# USBA1P_0v0.net
KiCad netlist of a schematic drawn in EAGLE
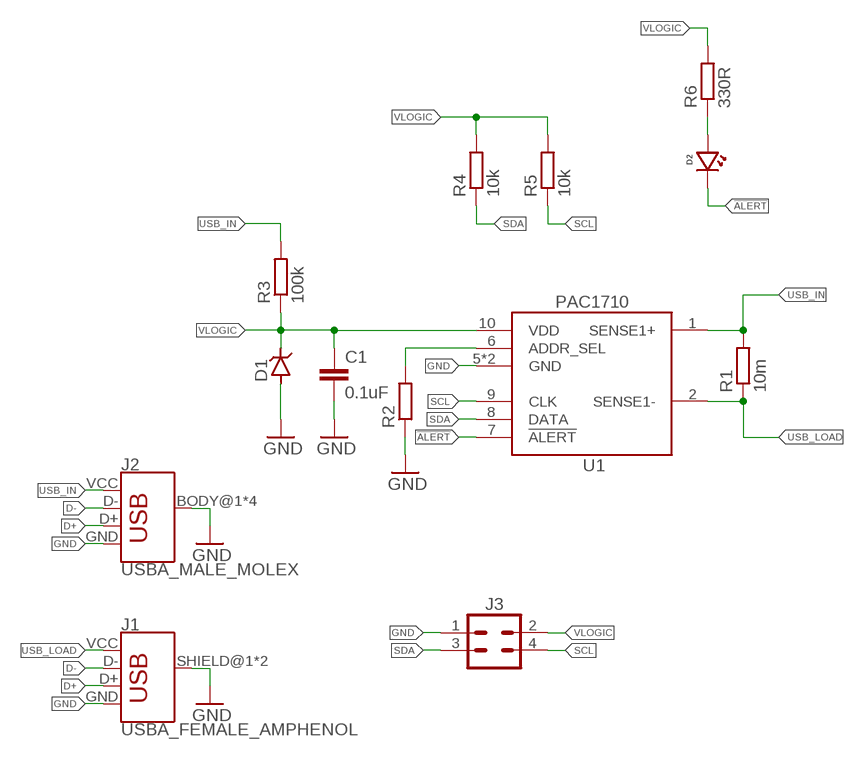
[diagram p0: schematic, sheet 1]

(export (version "E")
  (design (tool "Eeschema 10.0.6"))
  (components
    (comp (ref "C1")
      (value "0.1uF")
      (footprint "eagle-import:C0603")
      (fields (field (name "MF") "Murata") (field (name "MPN") "GCM188R71E104KA57D"))
      (libsource (lib "eagle-import") (part "C-EUC06030.1UF"))
    )
    (comp (ref "D1")
      (value "DIODE_ZENERSOD-123")
      (footprint "eagle-import:SOD-123")
      (libsource (lib "eagle-import") (part "DIODE_ZENERSOD-123"))
    )
    (comp (ref "D2")
      (value "LED1206_BOTTOM")
      (footprint "eagle-import:LED_1206_BOTTOM")
      (libsource (lib "eagle-import") (part "LED1206_BOTTOM"))
    )
    (comp (ref "J1")
      (value "USBA_FEMALE_AMPHENOL")
      (footprint "eagle-import:USB_A_FEMALE_AMPHENOL")
      (fields (field (name "MF") "Amphenol") (field (name "MPN") "UE27AC54100"))
      (libsource (lib "eagle-import") (part "USBA_FEMALE_AMPHENOL"))
    )
    (comp (ref "J2")
      (value "USBA_MALE_MOLEX")
      (footprint "eagle-import:USB_A_MALE_0480372200")
      (fields (field (name "MF") "Molex") (field (name "MPN") "0480372200"))
      (libsource (lib "eagle-import") (part "USBA_MALE_MOLEX"))
    )
    (comp (ref "J3")
      (value "CONN_2X2MIRCOFIT_RT")
      (footprint "eagle-import:2X2_MICROFIT_RT")
      (fields (field (name "MF") "Molex") (field (name "MPN") "0430450400"))
      (libsource (lib "eagle-import") (part "CONN_2X2MIRCOFIT_RT"))
    )
    (comp (ref "R1")
      (value "10m")
      (footprint "eagle-import:R0805")
      (fields (field (name "MF") "Bourns") (field (name "MPN") "CRF0805-FZ-R010ELF"))
      (libsource (lib "eagle-import") (part "R-EU_R08050.01"))
    )
    (comp (ref "R2")
      (value "R-EU_R0603")
      (footprint "eagle-import:R0603")
      (fields (field (name "MF") "Yageo"))
      (libsource (lib "eagle-import") (part "R-EU_R0603"))
    )
    (comp (ref "R3")
      (value "100k")
      (footprint "eagle-import:R0603")
      (fields (field (name "MF") "Yageo") (field (name "MPN") "RC0603FR-07100KL"))
      (libsource (lib "eagle-import") (part "R-EU_R0603100K"))
    )
    (comp (ref "R4")
      (value "10k")
      (footprint "eagle-import:R0603")
      (fields (field (name "MF") "Yageo") (field (name "MPN") "RC0603FR-0710KL"))
      (libsource (lib "eagle-import") (part "R-EU_R060310K"))
    )
    (comp (ref "R5")
      (value "10k")
      (footprint "eagle-import:R0603")
      (fields (field (name "MF") "Yageo") (field (name "MPN") "RC0603FR-0710KL"))
      (libsource (lib "eagle-import") (part "R-EU_R060310K"))
    )
    (comp (ref "R6")
      (value "330R")
      (footprint "eagle-import:R0603")
      (fields
        (field (name "MF") "Yageo")
        (field (name "MPN") "RC0603FR-07330RL")
        (field (name "VALUE_PART") "330")
      )
      (libsource (lib "eagle-import") (part "R-EU_R0603330"))
    )
    (comp (ref "U1")
      (value "PAC1710")
      (footprint "eagle-import:VDFN-10")
      (fields (field (name "MF") "Microchip") (field (name "MPN") "PAC1710-1-AIA-TR"))
      (libsource (lib "eagle-import") (part "PAC1710"))
    )
  )
  (nets
    (net (code "1") (name "/~{ALERT}") (class "Default")
      (node (ref "D2") (pin "CATHODE") (pinfunction "CATHODE_CATHODE") (pintype "power_in"))
      (node (ref "U1") (pin "7") (pinfunction "~{ALERT}_7") (pintype "output"))
    )
    (net (code "2") (name "D+") (class "Default")
      (node (ref "J1") (pin "D+") (pinfunction "D+_D+") (pintype "bidirectional"))
      (node (ref "J2") (pin "D+") (pinfunction "D+_D+") (pintype "bidirectional"))
    )
    (net (code "3") (name "D-") (class "Default")
      (node (ref "J1") (pin "D-") (pinfunction "D-_D-") (pintype "bidirectional"))
      (node (ref "J2") (pin "D-") (pinfunction "D-_D-") (pintype "bidirectional"))
    )
    (net (code "4") (name "GND") (class "Default")
      (node (ref "C1") (pin "2") (pinfunction "2_2") (pintype "passive"))
      (node (ref "D1") (pin "ANODE") (pinfunction "A_ANODE") (pintype "passive"))
      (node (ref "J1") (pin "GND") (pinfunction "GND_GND") (pintype "power_in"))
      (node (ref "J1") (pin "SHIELD@1") (pinfunction "SHIELD_SHIELD@1") (pintype "bidirectional"))
      (node (ref "J1") (pin "SHIELD@2") (pinfunction "SHIELD_SHIELD@2") (pintype "bidirectional"))
      (node (ref "J2") (pin "BODY@1") (pinfunction "SHIELD_BODY@1") (pintype "bidirectional"))
      (node (ref "J2") (pin "BODY@2") (pinfunction "SHIELD_BODY@2") (pintype "bidirectional"))
      (node (ref "J2") (pin "BODY@3") (pinfunction "SHIELD_BODY@3") (pintype "bidirectional"))
      (node (ref "J2") (pin "BODY@4") (pinfunction "SHIELD_BODY@4") (pintype "bidirectional"))
      (node (ref "J2") (pin "GND") (pinfunction "GND_GND") (pintype "power_in"))
      (node (ref "J3") (pin "1") (pinfunction "1_1") (pintype "bidirectional"))
      (node (ref "R2") (pin "1") (pinfunction "1_1") (pintype "passive"))
      (node (ref "U1") (pin "5") (pinfunction "GND_5") (pintype "power_in"))
      (node (ref "U1") (pin "EP") (pinfunction "GND_EP") (pintype "power_in"))
    )
    (net (code "5") (name "Net-(D2-PadANODE)") (class "Default")
      (node (ref "D2") (pin "ANODE") (pinfunction "ANODE_ANODE") (pintype "power_in"))
      (node (ref "R6") (pin "1") (pinfunction "1_1") (pintype "passive"))
    )
    (net (code "6") (name "Net-(U1-ADDR_SEL)") (class "Default")
      (node (ref "R2") (pin "2") (pinfunction "2_2") (pintype "passive"))
      (node (ref "U1") (pin "6") (pinfunction "ADDR_SEL_6") (pintype "input"))
    )
    (net (code "7") (name "SCL") (class "Default")
      (node (ref "J3") (pin "4") (pinfunction "4_4") (pintype "bidirectional"))
      (node (ref "R5") (pin "1") (pinfunction "1_1") (pintype "passive"))
      (node (ref "U1") (pin "9") (pinfunction "CLK_9") (pintype "input"))
    )
    (net (code "8") (name "SDA") (class "Default")
      (node (ref "J3") (pin "3") (pinfunction "3_3") (pintype "bidirectional"))
      (node (ref "R4") (pin "1") (pinfunction "1_1") (pintype "passive"))
      (node (ref "U1") (pin "8") (pinfunction "DATA_8") (pintype "bidirectional"))
    )
    (net (code "9") (name "USB_IN") (class "Default")
      (node (ref "J2") (pin "VCC") (pinfunction "VBUS_VCC") (pintype "power_in"))
      (node (ref "R1") (pin "2") (pinfunction "2_2") (pintype "passive"))
      (node (ref "R3") (pin "2") (pinfunction "2_2") (pintype "passive"))
      (node (ref "U1") (pin "1") (pinfunction "SENSE1+_1") (pintype "input"))
    )
    (net (code "10") (name "USB_LOAD") (class "Default")
      (node (ref "J1") (pin "VCC") (pinfunction "VBUS_VCC") (pintype "power_in"))
      (node (ref "R1") (pin "1") (pinfunction "1_1") (pintype "passive"))
      (node (ref "U1") (pin "2") (pinfunction "SENSE1-_2") (pintype "input"))
    )
    (net (code "11") (name "VLOGIC") (class "Default")
      (node (ref "C1") (pin "1") (pinfunction "1_1") (pintype "passive"))
      (node (ref "D1") (pin "CAT") (pinfunction "C_CAT") (pintype "passive"))
      (node (ref "J3") (pin "2") (pinfunction "2_2") (pintype "bidirectional"))
      (node (ref "R3") (pin "1") (pinfunction "1_1") (pintype "passive"))
      (node (ref "R4") (pin "2") (pinfunction "2_2") (pintype "passive"))
      (node (ref "R5") (pin "2") (pinfunction "2_2") (pintype "passive"))
      (node (ref "R6") (pin "2") (pinfunction "2_2") (pintype "passive"))
      (node (ref "U1") (pin "10") (pinfunction "VDD_10") (pintype "power_in"))
    )
  )
)
